# octanis_v0_2.net
KiCad netlist of a schematic drawn in EAGLE
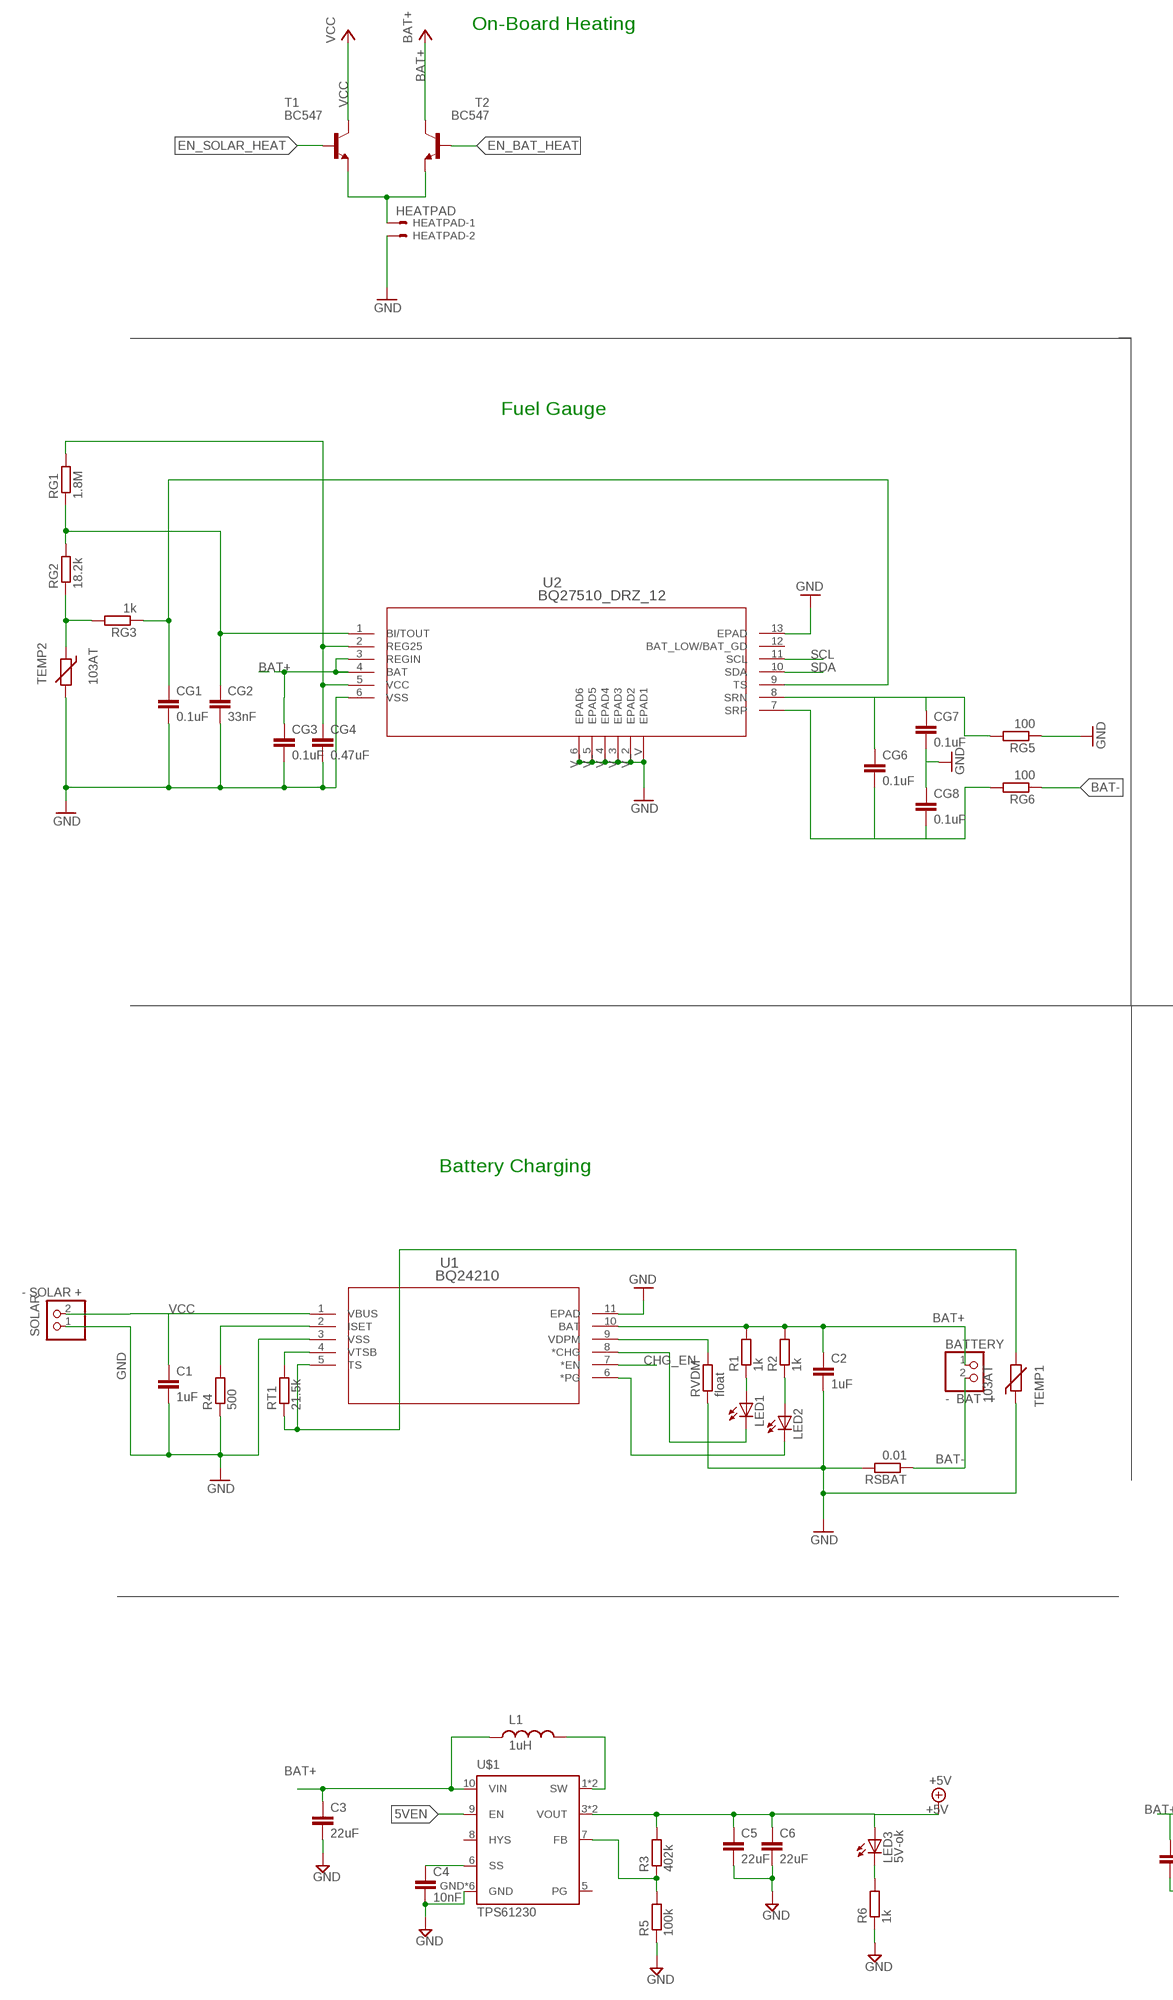
[diagram p0: schematic, sheet 1, part 1 of 3]
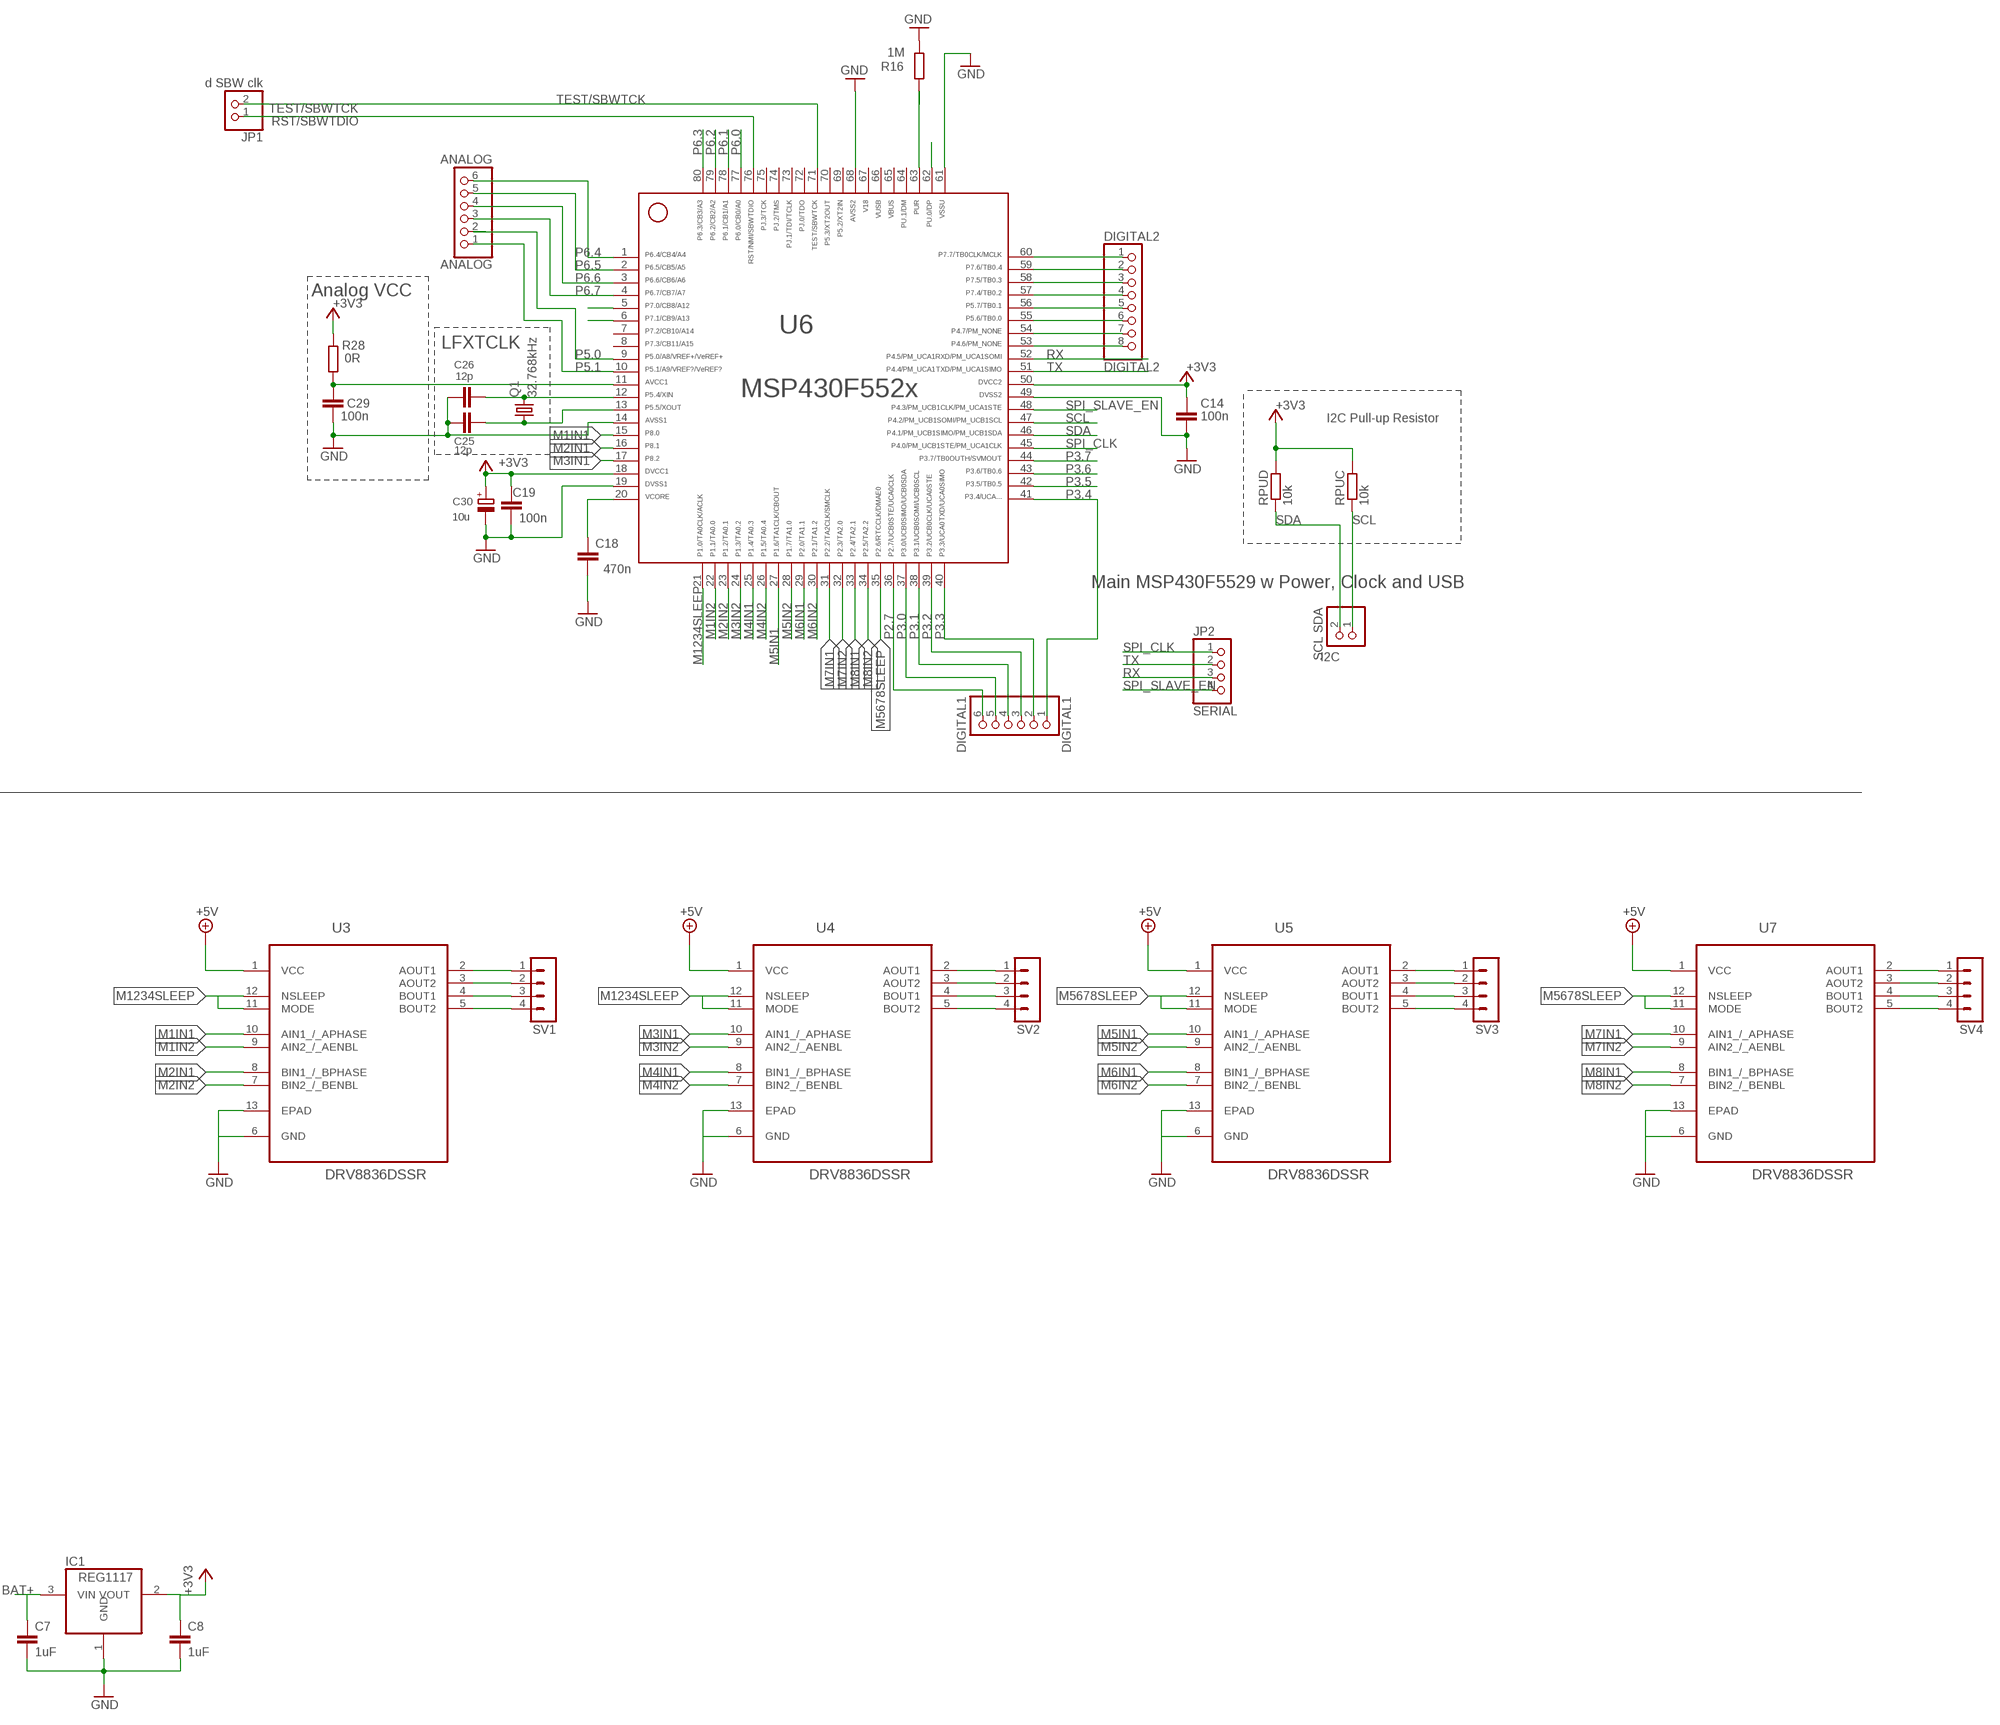
[diagram p1: schematic, sheet 1, part 2 of 3]
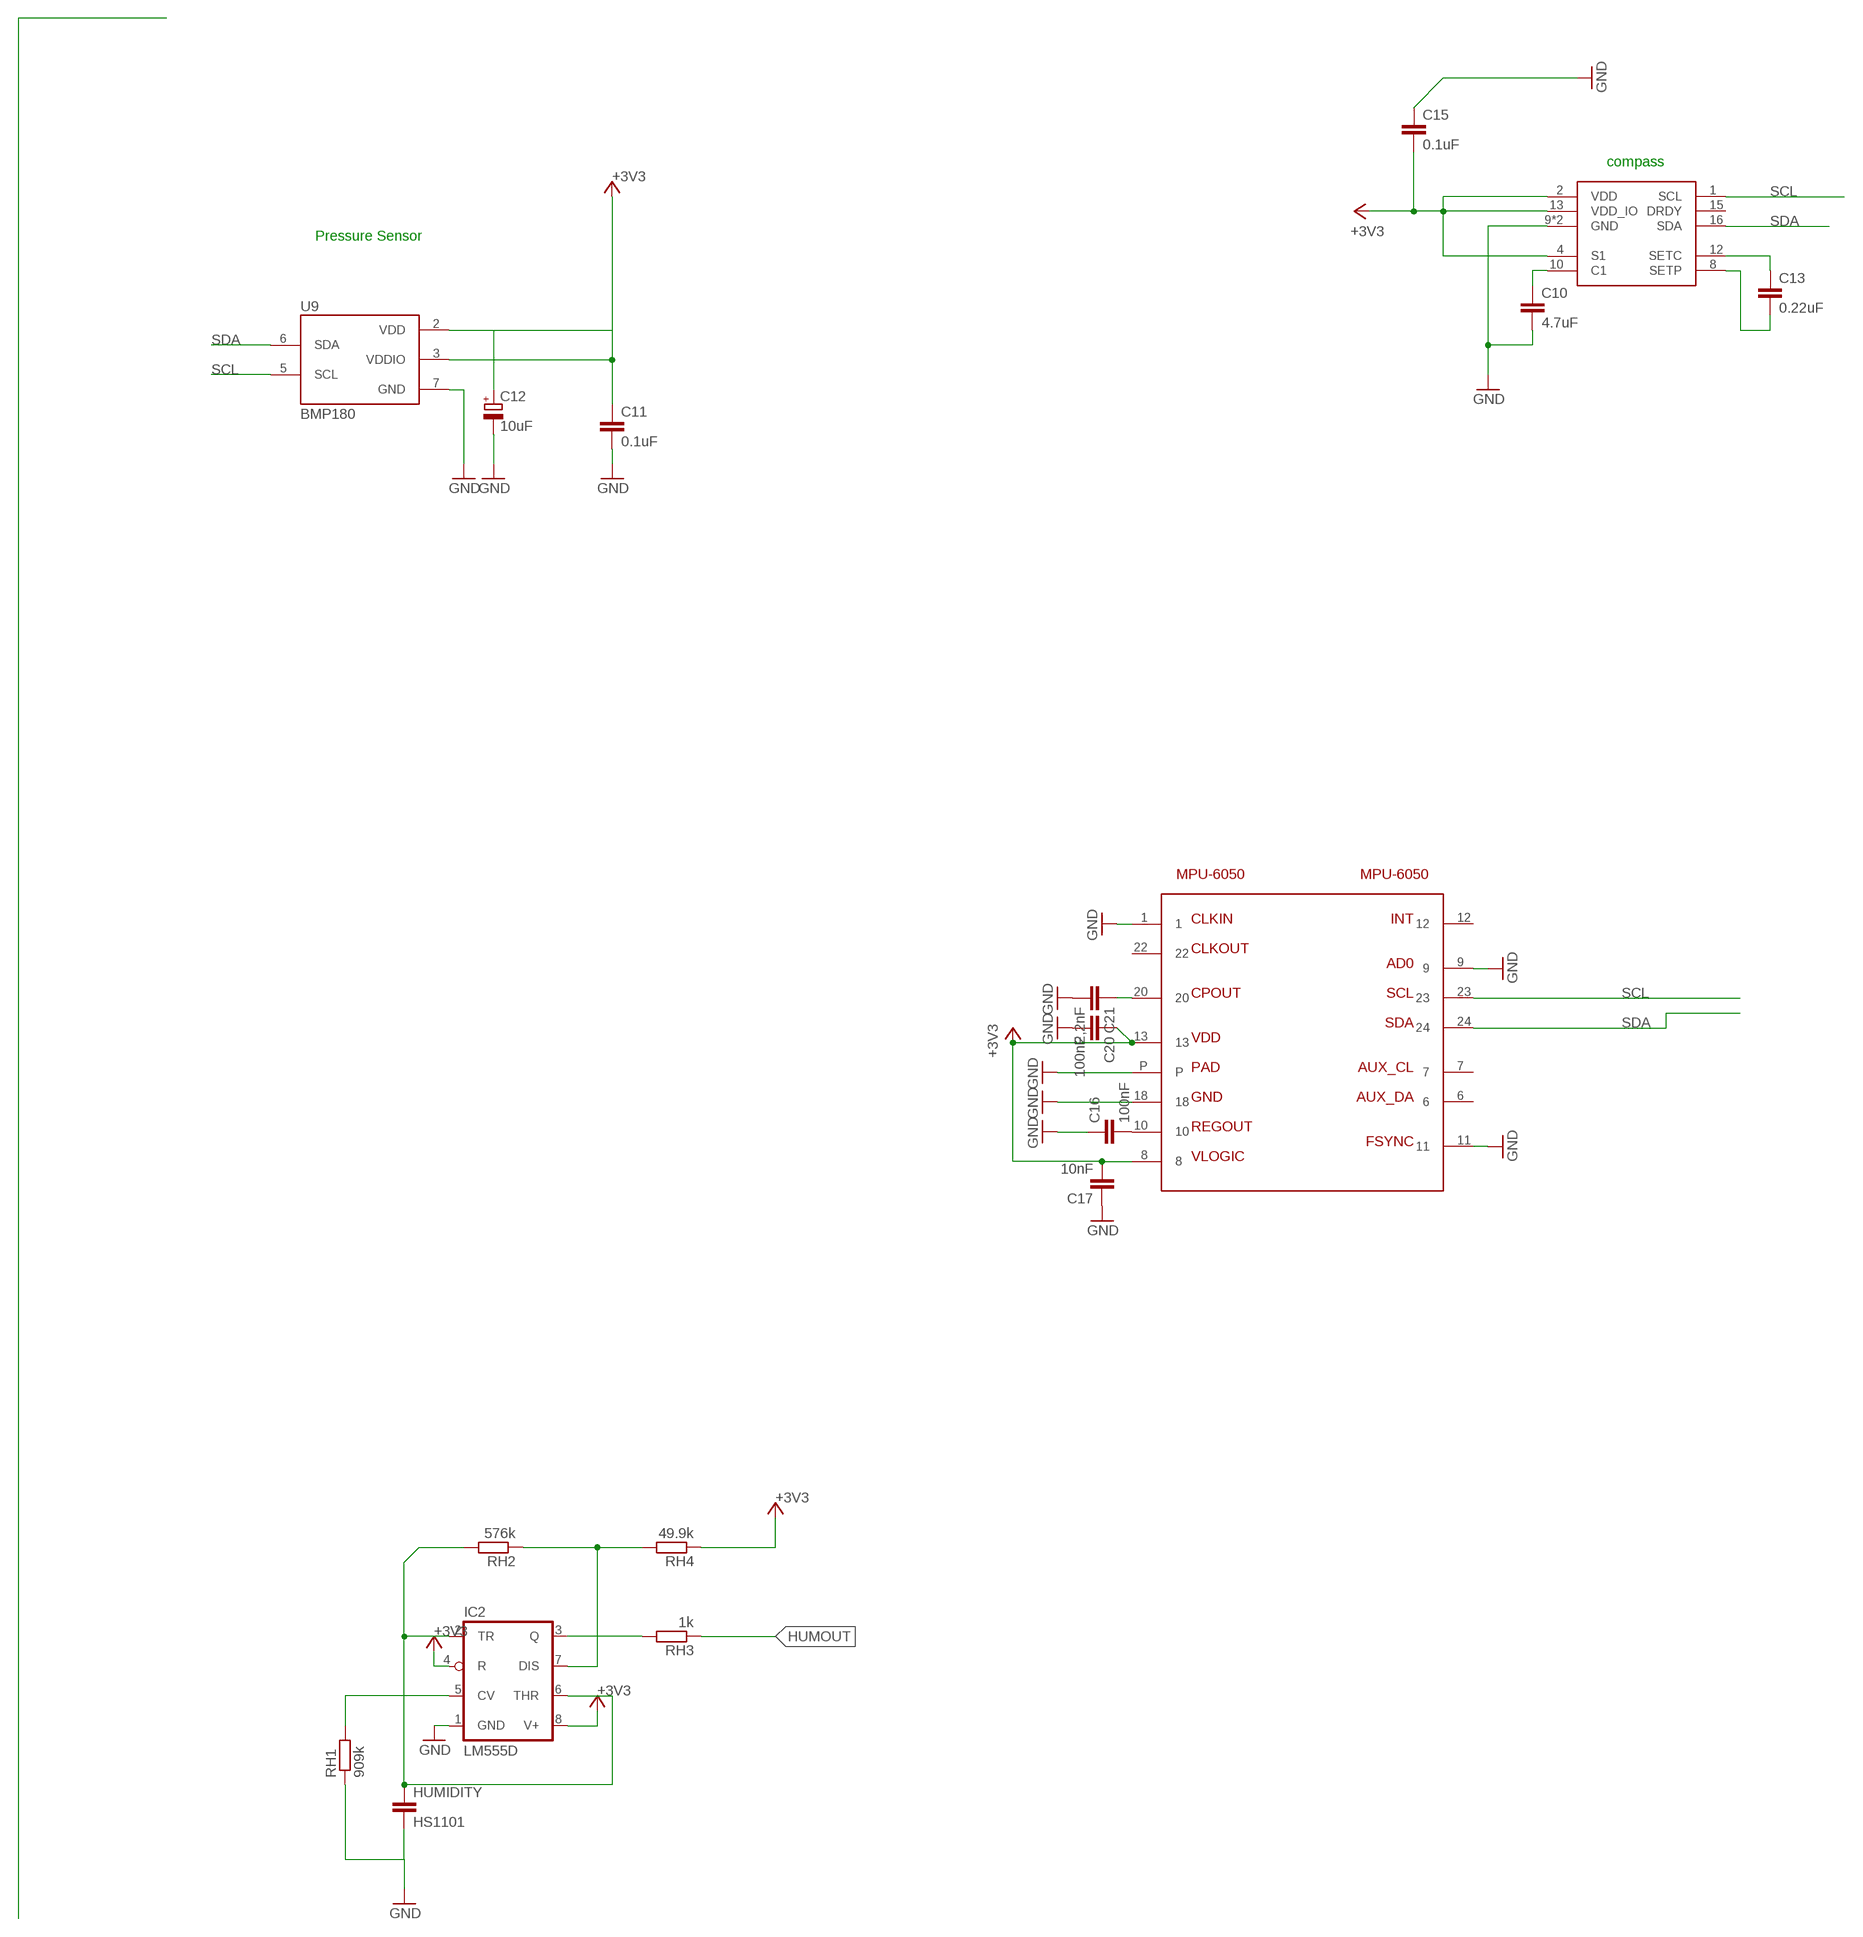
[diagram p2: schematic, sheet 1, part 3 of 3]

(export (version "E")
  (design (tool "Eeschema 10.0.6"))
  (components
    (comp (ref "ANALOG")
      (value "ANALOG")
      (footprint "eagle-import:1X06")
      (libsource (lib "eagle-import") (part "PINHD-1X6"))
    )
    (comp (ref "BATTERY")
      (value "- BAT +")
      (footprint "eagle-import:1X02")
      (libsource (lib "eagle-import") (part "PINHD-1X2"))
    )
    (comp (ref "C1")
      (value "1uF")
      (footprint "eagle-import:C1206")
      (libsource (lib "eagle-import") (part "C-EUC1206"))
    )
    (comp (ref "C2")
      (value "1uF")
      (footprint "eagle-import:C1206")
      (libsource (lib "eagle-import") (part "C-EUC1206"))
    )
    (comp (ref "C3")
      (value "22uF")
      (footprint "eagle-import:C0603")
      (libsource (lib "eagle-import") (part "C-EUC0603"))
    )
    (comp (ref "C4")
      (value "10nF")
      (footprint "eagle-import:C0603")
      (libsource (lib "eagle-import") (part "C-EUC0603"))
    )
    (comp (ref "C5")
      (value "22uF")
      (footprint "eagle-import:C0603")
      (libsource (lib "eagle-import") (part "C-EUC0603"))
    )
    (comp (ref "C6")
      (value "22uF")
      (footprint "eagle-import:C0603")
      (libsource (lib "eagle-import") (part "C-EUC0603"))
    )
    (comp (ref "C7")
      (value "1uF")
      (footprint "eagle-import:C0603")
      (libsource (lib "eagle-import") (part "C-EUC0603"))
    )
    (comp (ref "C8")
      (value "1uF")
      (footprint "eagle-import:C0603")
      (libsource (lib "eagle-import") (part "C-EUC0603"))
    )
    (comp (ref "C10")
      (value "4.7uF")
      (footprint "eagle-import:C0603")
      (libsource (lib "eagle-import") (part "C-EUC0603"))
    )
    (comp (ref "C11")
      (value "0.1uF")
      (footprint "eagle-import:C0603")
      (libsource (lib "eagle-import") (part "C-EUC0603"))
    )
    (comp (ref "C12")
      (value "10uF")
      (footprint "eagle-import:A_3216-18R")
      (libsource (lib "eagle-import") (part "resistor_CPOL-EUA/3216-18R"))
    )
    (comp (ref "C13")
      (value "0.22uF")
      (footprint "eagle-import:C0603")
      (libsource (lib "eagle-import") (part "C-EUC0603"))
    )
    (comp (ref "C14")
      (value "100n")
      (footprint "eagle-import:C0603")
      (libsource (lib "eagle-import") (part "C-EUC0603"))
    )
    (comp (ref "C15")
      (value "0.1uF")
      (footprint "eagle-import:C0603")
      (libsource (lib "eagle-import") (part "C-EUC0603"))
    )
    (comp (ref "C16")
      (value "100nF")
      (footprint "eagle-import:C0603")
      (libsource (lib "eagle-import") (part "C-EUC0603"))
    )
    (comp (ref "C17")
      (value "10nF")
      (footprint "eagle-import:C0603")
      (libsource (lib "eagle-import") (part "C-EUC0603"))
    )
    (comp (ref "C18")
      (value "470n")
      (footprint "eagle-import:C0603")
      (libsource (lib "eagle-import") (part "C-EUC0603"))
    )
    (comp (ref "C19")
      (value "100n")
      (footprint "eagle-import:C0603")
      (libsource (lib "eagle-import") (part "C-EUC0603"))
    )
    (comp (ref "C20")
      (value "100nF")
      (footprint "eagle-import:C0603")
      (libsource (lib "eagle-import") (part "C-EUC0603"))
    )
    (comp (ref "C21")
      (value "2,2nF")
      (footprint "eagle-import:C0603")
      (libsource (lib "eagle-import") (part "C-EUC0603"))
    )
    (comp (ref "C25")
      (value "12p")
      (footprint "eagle-import:C0603")
      (libsource (lib "eagle-import") (part "C-EUC0603"))
    )
    (comp (ref "C26")
      (value "12p")
      (footprint "eagle-import:C0603")
      (libsource (lib "eagle-import") (part "C-EUC0603"))
    )
    (comp (ref "C29")
      (value "100n")
      (footprint "eagle-import:C0603")
      (libsource (lib "eagle-import") (part "C-EUC0603"))
    )
    (comp (ref "C30")
      (value "10u")
      (footprint "eagle-import:A_3216-18R")
      (libsource (lib "eagle-import") (part "CPOL-EUA/3216-18R"))
    )
    (comp (ref "CG1")
      (value "0.1uF")
      (footprint "eagle-import:C0603")
      (libsource (lib "eagle-import") (part "C-EUC0603"))
    )
    (comp (ref "CG2")
      (value "33nF")
      (footprint "eagle-import:C0603")
      (libsource (lib "eagle-import") (part "C-EUC0603"))
    )
    (comp (ref "CG3")
      (value "0.1uF")
      (footprint "eagle-import:C0603")
      (libsource (lib "eagle-import") (part "C-EUC0603"))
    )
    (comp (ref "CG4")
      (value "0.47uF")
      (footprint "eagle-import:C0603")
      (libsource (lib "eagle-import") (part "C-EUC0603"))
    )
    (comp (ref "CG6")
      (value "0.1uF")
      (footprint "eagle-import:C0603")
      (libsource (lib "eagle-import") (part "C-EUC0603"))
    )
    (comp (ref "CG7")
      (value "0.1uF")
      (footprint "eagle-import:C0603")
      (libsource (lib "eagle-import") (part "C-EUC0603"))
    )
    (comp (ref "CG8")
      (value "0.1uF")
      (footprint "eagle-import:C0603")
      (libsource (lib "eagle-import") (part "C-EUC0603"))
    )
    (comp (ref "COMPASS")
      (value "HMC5883L")
      (footprint "eagle-import:LPCC16")
      (libsource (lib "eagle-import") (part "HMC5883L"))
    )
    (comp (ref "DIGITAL1")
      (value "DIGITAL1")
      (footprint "eagle-import:1X06")
      (libsource (lib "eagle-import") (part "PINHD-1X6"))
    )
    (comp (ref "DIGITAL2")
      (value "DIGITAL2")
      (footprint "eagle-import:1X08")
      (libsource (lib "eagle-import") (part "PINHD-1X8"))
    )
    (comp (ref "HEATPAD")
      (value "HEATPAD")
      (footprint "eagle-import:22-23-2021")
      (fields (field (name "MF") "MOLEX") (field (name "MPN") "22-23-2021"))
      (libsource (lib "eagle-import") (part "22-23-2021"))
    )
    (comp (ref "HUMIDITY")
      (value "HS1101")
      (footprint "eagle-import:C025-024X044")
      (libsource (lib "eagle-import") (part "C-EU025-024X044"))
    )
    (comp (ref "I2C")
      (value "SCL SDA")
      (footprint "eagle-import:1X02")
      (libsource (lib "eagle-import") (part "PINHD-1X2"))
    )
    (comp (ref "IC1")
      (value "REG1117")
      (footprint "eagle-import:SOT223")
      (libsource (lib "eagle-import") (part "REG1117"))
    )
    (comp (ref "IC2")
      (value "LM555D")
      (footprint "eagle-import:SO08")
      (libsource (lib "eagle-import") (part "555DLM"))
    )
    (comp (ref "JP1")
      (value "d SBW clk")
      (footprint "eagle-import:1X02")
      (libsource (lib "eagle-import") (part "PINHD-1X2"))
    )
    (comp (ref "JP2")
      (value "SERIAL")
      (footprint "eagle-import:1X04")
      (libsource (lib "eagle-import") (part "PINHD-1X4"))
    )
    (comp (ref "L1")
      (value "1uH")
      (footprint "eagle-import:XFL4020")
      (libsource (lib "eagle-import") (part "XFL4020"))
    )
    (comp (ref "LED1")
      (value "LEDCHIP-LED0603")
      (footprint "eagle-import:CHIP-LED0603")
      (libsource (lib "eagle-import") (part "led_LEDCHIP-LED0603"))
    )
    (comp (ref "LED2")
      (value "LEDCHIP-LED0603")
      (footprint "eagle-import:CHIP-LED0603")
      (libsource (lib "eagle-import") (part "led_LEDCHIP-LED0603"))
    )
    (comp (ref "LED3")
      (value "5V-ok")
      (footprint "eagle-import:CHIPLED_0603")
      (libsource (lib "eagle-import") (part "LEDCHIPLED_0603"))
    )
    (comp (ref "MPU-6050")
      (value "MPU-6050")
      (footprint "eagle-import:QFN24")
      (libsource (lib "eagle-import") (part "MPU-6050"))
    )
    (comp (ref "Q1")
      (value "32.768kHz")
      (footprint "eagle-import:FC-12M")
      (libsource (lib "eagle-import") (part "FC-12M"))
    )
    (comp (ref "R1")
      (value "1k")
      (footprint "eagle-import:R0603")
      (libsource (lib "eagle-import") (part "R-EU_R0603"))
    )
    (comp (ref "R2")
      (value "1k")
      (footprint "eagle-import:R0603")
      (libsource (lib "eagle-import") (part "R-EU_R0603"))
    )
    (comp (ref "R3")
      (value "402k")
      (footprint "eagle-import:R0603")
      (libsource (lib "eagle-import") (part "R-EU_R0603"))
    )
    (comp (ref "R4")
      (value "500")
      (footprint "eagle-import:R1206")
      (libsource (lib "eagle-import") (part "resistor_R-EU_R1206"))
    )
    (comp (ref "R5")
      (value "100k")
      (footprint "eagle-import:R0603")
      (libsource (lib "eagle-import") (part "R-EU_R0603"))
    )
    (comp (ref "R6")
      (value "1k")
      (footprint "eagle-import:R0603")
      (libsource (lib "eagle-import") (part "R-EU_R0603"))
    )
    (comp (ref "R16")
      (value "1M")
      (footprint "eagle-import:R0603")
      (libsource (lib "eagle-import") (part "R-EU_R0603"))
    )
    (comp (ref "R28")
      (value "0R")
      (footprint "eagle-import:R0603")
      (libsource (lib "eagle-import") (part "R-EU_R0603"))
    )
    (comp (ref "RG1")
      (value "1.8M")
      (footprint "eagle-import:R0603")
      (libsource (lib "eagle-import") (part "R-EU_R0603"))
    )
    (comp (ref "RG2")
      (value "18.2k")
      (footprint "eagle-import:R0603")
      (libsource (lib "eagle-import") (part "R-EU_R0603"))
    )
    (comp (ref "RG3")
      (value "1k")
      (footprint "eagle-import:R0603")
      (libsource (lib "eagle-import") (part "R-EU_R0603"))
    )
    (comp (ref "RG5")
      (value "100")
      (footprint "eagle-import:R0603")
      (libsource (lib "eagle-import") (part "R-EU_R0603"))
    )
    (comp (ref "RG6")
      (value "100")
      (footprint "eagle-import:R0603")
      (libsource (lib "eagle-import") (part "R-EU_R0603"))
    )
    (comp (ref "RH1")
      (value "909k")
      (footprint "eagle-import:R0603")
      (libsource (lib "eagle-import") (part "R-EU_R0603"))
    )
    (comp (ref "RH2")
      (value "576k")
      (footprint "eagle-import:R0603")
      (libsource (lib "eagle-import") (part "R-EU_R0603"))
    )
    (comp (ref "RH3")
      (value "1k")
      (footprint "eagle-import:R0603")
      (libsource (lib "eagle-import") (part "R-EU_R0603"))
    )
    (comp (ref "RH4")
      (value "49.9k")
      (footprint "eagle-import:R0603")
      (libsource (lib "eagle-import") (part "R-EU_R0603"))
    )
    (comp (ref "RPUC")
      (value "10k")
      (footprint "eagle-import:R0603")
      (libsource (lib "eagle-import") (part "R-EU_R0603"))
    )
    (comp (ref "RPUD")
      (value "10k")
      (footprint "eagle-import:R0603")
      (libsource (lib "eagle-import") (part "R-EU_R0603"))
    )
    (comp (ref "RSBAT")
      (value "0.01")
      (footprint "eagle-import:R1206")
      (libsource (lib "eagle-import") (part "resistor_R-EU_R1206"))
    )
    (comp (ref "RT1")
      (value "21.5k")
      (footprint "eagle-import:R1206")
      (libsource (lib "eagle-import") (part "resistor_R-EU_R1206"))
    )
    (comp (ref "RVDM")
      (value "float")
      (footprint "eagle-import:R1206")
      (libsource (lib "eagle-import") (part "resistor_R-EU_R1206"))
    )
    (comp (ref "SOLAR")
      (value "- SOLAR +")
      (footprint "eagle-import:1X02")
      (libsource (lib "eagle-import") (part "PINHD-1X2"))
    )
    (comp (ref "SV1")
      (value "MA04-1")
      (footprint "eagle-import:MA04-1")
      (libsource (lib "eagle-import") (part "MA04-1"))
    )
    (comp (ref "SV2")
      (value "MA04-1")
      (footprint "eagle-import:MA04-1")
      (libsource (lib "eagle-import") (part "MA04-1"))
    )
    (comp (ref "SV3")
      (value "MA04-1")
      (footprint "eagle-import:MA04-1")
      (libsource (lib "eagle-import") (part "MA04-1"))
    )
    (comp (ref "SV4")
      (value "MA04-1")
      (footprint "eagle-import:MA04-1")
      (libsource (lib "eagle-import") (part "MA04-1"))
    )
    (comp (ref "T1")
      (value "BC547")
      (footprint "eagle-import:TO92")
      (libsource (lib "eagle-import") (part "BC547"))
    )
    (comp (ref "T2")
      (value "BC547")
      (footprint "eagle-import:TO92")
      (libsource (lib "eagle-import") (part "BC547"))
    )
    (comp (ref "TEMP1")
      (value "103AT")
      (footprint "eagle-import:RS-2,5")
      (libsource (lib "eagle-import") (part "THERMISTOR-2,5"))
    )
    (comp (ref "TEMP2")
      (value "103AT")
      (footprint "eagle-import:RS-2,5")
      (libsource (lib "eagle-import") (part "THERMISTOR-2,5"))
    )
    (comp (ref "U$1")
      (value "TPS61230")
      (footprint "eagle-import:DRC-S-PVSON-N11")
      (libsource (lib "eagle-import") (part "TPS61230"))
    )
    (comp (ref "U1")
      (value "BQ24210")
      (footprint "eagle-import:DQC10_P84X2P4")
      (fields (field (name "MANUFACTURER") "Texas Instruments"))
      (libsource (lib "eagle-import") (part "BQ24210_DQC_10"))
    )
    (comp (ref "U2")
      (value "BQ27510_DRZ_12")
      (footprint "eagle-import:DRZ12_1P95X2P45")
      (fields
        (field (name "GENERIC_PART_NUMBER") "BQ27510")
        (field (name "MANUFACTURER") "Texas Instruments")
      )
      (libsource (lib "eagle-import") (part "BQ27510_DRZ_12"))
    )
    (comp (ref "U3")
      (value "DRV8836DSSR")
      (footprint "eagle-import:SON50P200X300X80-13N")
      (fields (field (name "MPN") "DRV8836DSSR "))
      (libsource (lib "eagle-import") (part "DRV8836DSSR"))
    )
    (comp (ref "U4")
      (value "DRV8836DSSR")
      (footprint "eagle-import:SON50P200X300X80-13N")
      (fields (field (name "MPN") "DRV8836DSSR "))
      (libsource (lib "eagle-import") (part "DRV8836DSSR"))
    )
    (comp (ref "U5")
      (value "DRV8836DSSR")
      (footprint "eagle-import:SON50P200X300X80-13N")
      (fields (field (name "MPN") "DRV8836DSSR "))
      (libsource (lib "eagle-import") (part "DRV8836DSSR"))
    )
    (comp (ref "U6")
      (value "MSP430F5529IPNR")
      (footprint "eagle-import:PN80")
      (libsource (lib "eagle-import") (part "F552X---PN80"))
    )
    (comp (ref "U7")
      (value "DRV8836DSSR")
      (footprint "eagle-import:SON50P200X300X80-13N")
      (fields (field (name "MPN") "DRV8836DSSR "))
      (libsource (lib "eagle-import") (part "DRV8836DSSR"))
    )
    (comp (ref "U9")
      (value "BMP180")
      (footprint "eagle-import:BMP180")
      (libsource (lib "eagle-import") (part "BMP180"))
    )
  )
  (nets
    (net (code "1") (name "+3V3") (class "Default")
      (node (ref "C11") (pin "1") (pinfunction "1_1") (pintype "passive"))
      (node (ref "C12") (pin "+") (pinfunction "+_+") (pintype "passive"))
      (node (ref "C14") (pin "1") (pinfunction "1_1") (pintype "passive"))
      (node (ref "C15") (pin "2") (pinfunction "2_2") (pintype "passive"))
      (node (ref "C17") (pin "2") (pinfunction "2_2") (pintype "passive"))
      (node (ref "C19") (pin "2") (pinfunction "2_2") (pintype "passive"))
      (node (ref "C20") (pin "1") (pinfunction "1_1") (pintype "passive"))
      (node (ref "C30") (pin "+") (pinfunction "+_+") (pintype "passive"))
      (node (ref "C8") (pin "1") (pinfunction "1_1") (pintype "passive"))
      (node (ref "COMPASS") (pin "13") (pinfunction "VDD_IO_13") (pintype "power_in"))
      (node (ref "COMPASS") (pin "2") (pinfunction "VDD_2") (pintype "power_in"))
      (node (ref "COMPASS") (pin "4") (pinfunction "S1_4") (pintype "power_in"))
      (node (ref "IC1") (pin "2") (pinfunction "VOUT_2") (pintype "output"))
      (node (ref "IC2") (pin "4") (pinfunction "R_4") (pintype "input"))
      (node (ref "IC2") (pin "8") (pinfunction "V+_8") (pintype "power_in"))
      (node (ref "MPU-6050") (pin "13") (pinfunction "13_13") (pintype "bidirectional"))
      (node (ref "MPU-6050") (pin "8") (pinfunction "8_8") (pintype "bidirectional"))
      (node (ref "R28") (pin "2") (pinfunction "2_2") (pintype "passive"))
      (node (ref "RH4") (pin "1") (pinfunction "1_1") (pintype "passive"))
      (node (ref "RPUC") (pin "2") (pinfunction "2_2") (pintype "passive"))
      (node (ref "RPUD") (pin "2") (pinfunction "2_2") (pintype "passive"))
      (node (ref "U6") (pin "18") (pinfunction "18_18") (pintype "power_in"))
      (node (ref "U6") (pin "50") (pinfunction "50_50") (pintype "power_in"))
      (node (ref "U9") (pin "2") (pinfunction "VDD_2") (pintype "power_in"))
      (node (ref "U9") (pin "3") (pinfunction "VDDIO_3") (pintype "power_in"))
    )
    (net (code "2") (name "+5V") (class "Default")
      (node (ref "C5") (pin "1") (pinfunction "1_1") (pintype "passive"))
      (node (ref "C6") (pin "1") (pinfunction "1_1") (pintype "passive"))
      (node (ref "LED3") (pin "A") (pinfunction "A_A") (pintype "passive"))
      (node (ref "R3") (pin "2") (pinfunction "2_2") (pintype "passive"))
      (node (ref "U$1") (pin "3") (pinfunction "VOUT_3") (pintype "passive"))
      (node (ref "U$1") (pin "4") (pinfunction "VOUT_4") (pintype "passive"))
      (node (ref "U3") (pin "1") (pinfunction "VCC_1") (pintype "power_in"))
      (node (ref "U4") (pin "1") (pinfunction "VCC_1") (pintype "power_in"))
      (node (ref "U5") (pin "1") (pinfunction "VCC_1") (pintype "power_in"))
      (node (ref "U7") (pin "1") (pinfunction "VCC_1") (pintype "power_in"))
    )
    (net (code "3") (name "/65") (class "Default")
      (node (ref "U6") (pin "65") (pinfunction "65_65") (pintype "power_in"))
    )
    (net (code "4") (name "/66") (class "Default")
      (node (ref "U6") (pin "66") (pinfunction "66_66") (pintype "power_in"))
    )
    (net (code "5") (name "/67") (class "Default")
      (node (ref "U6") (pin "67") (pinfunction "67_67") (pintype "power_in"))
    )
    (net (code "6") (name "/CHG_EN") (class "Default")
      (node (ref "U1") (pin "7") (pinfunction "*EN_7") (pintype "input"))
      (node (ref "U6") (pin "5") (pinfunction "5_5") (pintype "bidirectional"))
    )
    (net (code "7") (name "/P2.7") (class "Default")
      (node (ref "DIGITAL1") (pin "6") (pinfunction "6_6") (pintype "passive"))
      (node (ref "U6") (pin "36") (pinfunction "36_36") (pintype "bidirectional"))
    )
    (net (code "8") (name "/P3.0") (class "Default")
      (node (ref "DIGITAL1") (pin "5") (pinfunction "5_5") (pintype "passive"))
      (node (ref "U6") (pin "37") (pinfunction "37_37") (pintype "bidirectional"))
    )
    (net (code "9") (name "/P3.1") (class "Default")
      (node (ref "DIGITAL1") (pin "4") (pinfunction "4_4") (pintype "passive"))
      (node (ref "U6") (pin "38") (pinfunction "38_38") (pintype "bidirectional"))
    )
    (net (code "10") (name "/P3.2") (class "Default")
      (node (ref "DIGITAL1") (pin "3") (pinfunction "3_3") (pintype "passive"))
      (node (ref "U6") (pin "39") (pinfunction "39_39") (pintype "bidirectional"))
    )
    (net (code "11") (name "/P3.3") (class "Default")
      (node (ref "DIGITAL1") (pin "2") (pinfunction "2_2") (pintype "passive"))
      (node (ref "U6") (pin "40") (pinfunction "40_40") (pintype "bidirectional"))
    )
    (net (code "12") (name "/P3.4") (class "Default")
      (node (ref "DIGITAL1") (pin "1") (pinfunction "1_1") (pintype "passive"))
      (node (ref "U6") (pin "41") (pinfunction "41_41") (pintype "bidirectional"))
    )
    (net (code "13") (name "/P3.5") (class "Default")
      (node (ref "U6") (pin "42") (pinfunction "42_42") (pintype "bidirectional"))
    )
    (net (code "14") (name "/P3.6") (class "Default")
      (node (ref "U6") (pin "43") (pinfunction "43_43") (pintype "bidirectional"))
    )
    (net (code "15") (name "/P3.7") (class "Default")
      (node (ref "U6") (pin "44") (pinfunction "44_44") (pintype "bidirectional"))
    )
    (net (code "16") (name "/P5.0") (class "Default")
      (node (ref "ANALOG") (pin "2") (pinfunction "2_2") (pintype "passive"))
      (node (ref "U6") (pin "9") (pinfunction "9_9") (pintype "bidirectional"))
    )
    (net (code "17") (name "/P5.1") (class "Default")
      (node (ref "ANALOG") (pin "1") (pinfunction "1_1") (pintype "passive"))
      (node (ref "U6") (pin "10") (pinfunction "10_10") (pintype "bidirectional"))
    )
    (net (code "18") (name "/P6.0") (class "Default")
      (node (ref "U6") (pin "77") (pinfunction "77_77") (pintype "bidirectional"))
    )
    (net (code "19") (name "/P6.1") (class "Default")
      (node (ref "U6") (pin "78") (pinfunction "78_78") (pintype "bidirectional"))
    )
    (net (code "20") (name "/P6.2") (class "Default")
      (node (ref "U6") (pin "79") (pinfunction "79_79") (pintype "bidirectional"))
    )
    (net (code "21") (name "/P6.3") (class "Default")
      (node (ref "U6") (pin "80") (pinfunction "80_80") (pintype "bidirectional"))
    )
    (net (code "22") (name "/P6.4") (class "Default")
      (node (ref "ANALOG") (pin "6") (pinfunction "6_6") (pintype "passive"))
      (node (ref "U6") (pin "1") (pinfunction "1_1") (pintype "bidirectional"))
    )
    (net (code "23") (name "/P6.5") (class "Default")
      (node (ref "ANALOG") (pin "5") (pinfunction "5_5") (pintype "passive"))
      (node (ref "U6") (pin "2") (pinfunction "2_2") (pintype "bidirectional"))
    )
    (net (code "24") (name "/P6.6") (class "Default")
      (node (ref "ANALOG") (pin "4") (pinfunction "4_4") (pintype "passive"))
      (node (ref "U6") (pin "3") (pinfunction "3_3") (pintype "bidirectional"))
    )
    (net (code "25") (name "/P6.7") (class "Default")
      (node (ref "ANALOG") (pin "3") (pinfunction "3_3") (pintype "passive"))
      (node (ref "U6") (pin "4") (pinfunction "4_4") (pintype "bidirectional"))
    )
    (net (code "26") (name "/PG") (class "Default")
      (node (ref "U$1") (pin "5") (pinfunction "PG_5") (pintype "power_in"))
    )
    (net (code "27") (name "/RST{slash}SBWTDIO") (class "Default")
      (node (ref "JP1") (pin "1") (pinfunction "1_1") (pintype "passive"))
      (node (ref "U6") (pin "76") (pinfunction "76_76") (pintype "bidirectional"))
    )
    (net (code "28") (name "/RX") (class "Default")
      (node (ref "JP2") (pin "3") (pinfunction "3_3") (pintype "passive"))
      (node (ref "U6") (pin "52") (pinfunction "52_52") (pintype "bidirectional"))
    )
    (net (code "29") (name "/SCL") (class "Default")
      (node (ref "COMPASS") (pin "1") (pinfunction "SCL_1") (pintype "input"))
      (node (ref "I2C") (pin "1") (pinfunction "1_1") (pintype "passive"))
      (node (ref "MPU-6050") (pin "23") (pinfunction "23_23") (pintype "bidirectional"))
      (node (ref "RPUC") (pin "1") (pinfunction "1_1") (pintype "passive"))
      (node (ref "U2") (pin "11") (pinfunction "SCL_11") (pintype "input"))
      (node (ref "U6") (pin "47") (pinfunction "47_47") (pintype "bidirectional"))
      (node (ref "U9") (pin "5") (pinfunction "SCL_5") (pintype "input"))
    )
    (net (code "30") (name "/SDA") (class "Default")
      (node (ref "COMPASS") (pin "16") (pinfunction "SDA_16") (pintype "input"))
      (node (ref "I2C") (pin "2") (pinfunction "2_2") (pintype "passive"))
      (node (ref "MPU-6050") (pin "24") (pinfunction "24_24") (pintype "bidirectional"))
      (node (ref "RPUD") (pin "1") (pinfunction "1_1") (pintype "passive"))
      (node (ref "U2") (pin "10") (pinfunction "SDA_10") (pintype "bidirectional"))
      (node (ref "U6") (pin "46") (pinfunction "46_46") (pintype "bidirectional"))
      (node (ref "U9") (pin "6") (pinfunction "SDA_6") (pintype "bidirectional"))
    )
    (net (code "31") (name "/SPI_CLK") (class "Default")
      (node (ref "JP2") (pin "1") (pinfunction "1_1") (pintype "passive"))
      (node (ref "U6") (pin "45") (pinfunction "45_45") (pintype "bidirectional"))
    )
    (net (code "32") (name "/SPI_SLAVE_EN") (class "Default")
      (node (ref "JP2") (pin "4") (pinfunction "4_4") (pintype "passive"))
      (node (ref "U6") (pin "48") (pinfunction "48_48") (pintype "bidirectional"))
    )
    (net (code "33") (name "/TEST{slash}SBWTCK") (class "Default")
      (node (ref "JP1") (pin "2") (pinfunction "2_2") (pintype "passive"))
      (node (ref "U6") (pin "71") (pinfunction "71_71") (pintype "input"))
    )
    (net (code "34") (name "/TX") (class "Default")
      (node (ref "JP2") (pin "2") (pinfunction "2_2") (pintype "passive"))
      (node (ref "U6") (pin "51") (pinfunction "51_51") (pintype "bidirectional"))
    )
    (net (code "35") (name "5VEN") (class "Default")
      (node (ref "U$1") (pin "9") (pinfunction "EN_9") (pintype "input"))
      (node (ref "U6") (pin "6") (pinfunction "6_6") (pintype "bidirectional"))
    )
    (net (code "36") (name "BAT+") (class "Default")
      (node (ref "BATTERY") (pin "1") (pinfunction "1_1") (pintype "passive"))
      (node (ref "C2") (pin "1") (pinfunction "1_1") (pintype "passive"))
      (node (ref "C3") (pin "1") (pinfunction "1_1") (pintype "passive"))
      (node (ref "C7") (pin "1") (pinfunction "1_1") (pintype "passive"))
      (node (ref "CG3") (pin "1") (pinfunction "1_1") (pintype "passive"))
      (node (ref "IC1") (pin "3") (pinfunction "VIN_3") (pintype "input"))
      (node (ref "L1") (pin "P$1") (pinfunction "1_P$1") (pintype "passive"))
      (node (ref "R1") (pin "2") (pinfunction "2_2") (pintype "passive"))
      (node (ref "R2") (pin "2") (pinfunction "2_2") (pintype "passive"))
      (node (ref "T2") (pin "3") (pinfunction "C_3") (pintype "passive"))
      (node (ref "U$1") (pin "10") (pinfunction "VIN_10") (pintype "input"))
      (node (ref "U1") (pin "10") (pinfunction "BAT_10") (pintype "bidirectional"))
      (node (ref "U2") (pin "3") (pinfunction "REGIN_3") (pintype "power_in"))
      (node (ref "U2") (pin "4") (pinfunction "BAT_4") (pintype "input"))
    )
    (net (code "37") (name "BAT-") (class "Default")
      (node (ref "BATTERY") (pin "2") (pinfunction "2_2") (pintype "passive"))
      (node (ref "RG6") (pin "1") (pinfunction "1_1") (pintype "passive"))
      (node (ref "RSBAT") (pin "1") (pinfunction "1_1") (pintype "passive"))
    )
    (net (code "38") (name "EN_BAT_HEAT") (class "Default")
      (node (ref "T2") (pin "2") (pinfunction "B_2") (pintype "passive"))
    )
    (net (code "39") (name "EN_SOLAR_HEAT") (class "Default")
      (node (ref "T1") (pin "2") (pinfunction "B_2") (pintype "passive"))
    )
    (net (code "40") (name "GND") (class "Default")
      (node (ref "C1") (pin "2") (pinfunction "2_2") (pintype "passive"))
      (node (ref "C10") (pin "2") (pinfunction "2_2") (pintype "passive"))
      (node (ref "C11") (pin "2") (pinfunction "2_2") (pintype "passive"))
      (node (ref "C12") (pin "-") (pinfunction "-_-") (pintype "passive"))
      (node (ref "C14") (pin "2") (pinfunction "2_2") (pintype "passive"))
      (node (ref "C15") (pin "1") (pinfunction "1_1") (pintype "passive"))
      (node (ref "C16") (pin "1") (pinfunction "1_1") (pintype "passive"))
      (node (ref "C17") (pin "1") (pinfunction "1_1") (pintype "passive"))
      (node (ref "C18") (pin "1") (pinfunction "1_1") (pintype "passive"))
      (node (ref "C19") (pin "1") (pinfunction "1_1") (pintype "passive"))
      (node (ref "C2") (pin "2") (pinfunction "2_2") (pintype "passive"))
      (node (ref "C20") (pin "2") (pinfunction "2_2") (pintype "passive"))
      (node (ref "C21") (pin "2") (pinfunction "2_2") (pintype "passive"))
      (node (ref "C25") (pin "1") (pinfunction "1_1") (pintype "passive"))
      (node (ref "C26") (pin "1") (pinfunction "1_1") (pintype "passive"))
      (node (ref "C29") (pin "2") (pinfunction "2_2") (pintype "passive"))
      (node (ref "C3") (pin "2") (pinfunction "2_2") (pintype "passive"))
      (node (ref "C30") (pin "-") (pinfunction "-_-") (pintype "passive"))
      (node (ref "C4") (pin "2") (pinfunction "2_2") (pintype "passive"))
      (node (ref "C5") (pin "2") (pinfunction "2_2") (pintype "passive"))
      (node (ref "C6") (pin "2") (pinfunction "2_2") (pintype "passive"))
      (node (ref "C7") (pin "2") (pinfunction "2_2") (pintype "passive"))
      (node (ref "C8") (pin "2") (pinfunction "2_2") (pintype "passive"))
      (node (ref "CG1") (pin "2") (pinfunction "2_2") (pintype "passive"))
      (node (ref "CG2") (pin "2") (pinfunction "2_2") (pintype "passive"))
      (node (ref "CG3") (pin "2") (pinfunction "2_2") (pintype "passive"))
      (node (ref "CG4") (pin "2") (pinfunction "2_2") (pintype "passive"))
      (node (ref "CG7") (pin "2") (pinfunction "2_2") (pintype "passive"))
      (node (ref "CG8") (pin "1") (pinfunction "1_1") (pintype "passive"))
      (node (ref "COMPASS") (pin "11") (pinfunction "GND_11") (pintype "bidirectional"))
      (node (ref "COMPASS") (pin "9") (pinfunction "GND_9") (pintype "bidirectional"))
      (node (ref "HEATPAD") (pin "2") (pinfunction "S_2") (pintype "passive"))
      (node (ref "HUMIDITY") (pin "2") (pinfunction "2_2") (pintype "passive"))
      (node (ref "IC1") (pin "1") (pinfunction "GND_1") (pintype "power_in"))
      (node (ref "IC2") (pin "1") (pinfunction "GND_1") (pintype "power_in"))
      (node (ref "MPU-6050") (pin "1") (pinfunction "1_1") (pintype "bidirectional"))
      (node (ref "MPU-6050") (pin "11") (pinfunction "11_11") (pintype "bidirectional"))
      (node (ref "MPU-6050") (pin "18") (pinfunction "18_18") (pintype "bidirectional"))
      (node (ref "MPU-6050") (pin "9") (pinfunction "9_9") (pintype "bidirectional"))
      (node (ref "MPU-6050") (pin "P") (pinfunction "P_P") (pintype "bidirectional"))
      (node (ref "R16") (pin "1") (pinfunction "1_1") (pintype "passive"))
      (node (ref "R4") (pin "1") (pinfunction "1_1") (pintype "passive"))
      (node (ref "R5") (pin "1") (pinfunction "1_1") (pintype "passive"))
      (node (ref "R6") (pin "1") (pinfunction "1_1") (pintype "passive"))
      (node (ref "RG5") (pin "1") (pinfunction "1_1") (pintype "passive"))
      (node (ref "RH1") (pin "1") (pinfunction "1_1") (pintype "passive"))
      (node (ref "RSBAT") (pin "2") (pinfunction "2_2") (pintype "passive"))
      (node (ref "RVDM") (pin "1") (pinfunction "1_1") (pintype "passive"))
      (node (ref "SOLAR") (pin "1") (pinfunction "1_1") (pintype "passive"))
      (node (ref "TEMP1") (pin "1") (pinfunction "1_1") (pintype "passive"))
      (node (ref "TEMP2") (pin "2") (pinfunction "2_2") (pintype "passive"))
      (node (ref "U$1") (pin "GND") (pinfunction "GND_GND") (pintype "power_in"))
      (node (ref "U$1") (pin "GND@1") (pinfunction "GND_GND@1") (pintype "power_in"))
      (node (ref "U$1") (pin "GND@2") (pinfunction "GND_GND@2") (pintype "power_in"))
      (node (ref "U$1") (pin "GND@3") (pinfunction "GND_GND@3") (pintype "power_in"))
      (node (ref "U$1") (pin "GND@4") (pinfunction "GND_GND@4") (pintype "power_in"))
      (node (ref "U$1") (pin "GND@5") (pinfunction "GND_GND@5") (pintype "power_in"))
      (node (ref "U1") (pin "11") (pinfunction "EPAD_11") (pintype "power_in"))
      (node (ref "U1") (pin "3") (pinfunction "VSS_3") (pintype "power_in"))
      (node (ref "U2") (pin "13") (pinfunction "EPAD_13") (pintype "power_in"))
      (node (ref "U2") (pin "6") (pinfunction "VSS_6") (pintype "power_in"))
      (node (ref "U2") (pin "V") (pinfunction "EPAD1_V") (pintype "power_in"))
      (node (ref "U2") (pin "V_2") (pinfunction "EPAD2_V_2") (pintype "power_in"))
      (node (ref "U2") (pin "V_3") (pinfunction "EPAD3_V_3") (pintype "power_in"))
      (node (ref "U2") (pin "V_4") (pinfunction "EPAD4_V_4") (pintype "power_in"))
      (node (ref "U2") (pin "V_5") (pinfunction "EPAD5_V_5") (pintype "power_in"))
      (node (ref "U2") (pin "V_6") (pinfunction "EPAD6_V_6") (pintype "power_in"))
      (node (ref "U3") (pin "13") (pinfunction "EPAD_13") (pintype "passive"))
      (node (ref "U3") (pin "6") (pinfunction "GND_6") (pintype "passive"))
      (node (ref "U4") (pin "13") (pinfunction "EPAD_13") (pintype "passive"))
      (node (ref "U4") (pin "6") (pinfunction "GND_6") (pintype "passive"))
      (node (ref "U5") (pin "13") (pinfunction "EPAD_13") (pintype "passive"))
      (node (ref "U5") (pin "6") (pinfunction "GND_6") (pintype "passive"))
      (node (ref "U6") (pin "14") (pinfunction "14_14") (pintype "power_in"))
      (node (ref "U6") (pin "19") (pinfunction "19_19") (pintype "power_in"))
      (node (ref "U6") (pin "49") (pinfunction "49_49") (pintype "power_in"))
      (node (ref "U6") (pin "61") (pinfunction "61_61") (pintype "power_in"))
      (node (ref "U6") (pin "68") (pinfunction "68_68") (pintype "power_in"))
      (node (ref "U7") (pin "13") (pinfunction "EPAD_13") (pintype "passive"))
      (node (ref "U7") (pin "6") (pinfunction "GND_6") (pintype "passive"))
      (node (ref "U9") (pin "7") (pinfunction "GND_7") (pintype "power_in"))
    )
    (net (code "41") (name "HUMOUT") (class "Default")
      (node (ref "RH3") (pin "1") (pinfunction "1_1") (pintype "passive"))
    )
    (net (code "42") (name "M1IN1") (class "Default")
      (node (ref "U3") (pin "10") (pinfunction "AIN1_/_APHASE_10") (pintype "input"))
      (node (ref "U6") (pin "15") (pinfunction "15_15") (pintype "bidirectional"))
    )
    (net (code "43") (name "M1IN2") (class "Default")
      (node (ref "U3") (pin "9") (pinfunction "AIN2_/_AENBL_9") (pintype "input"))
      (node (ref "U6") (pin "22") (pinfunction "22_22") (pintype "bidirectional"))
    )
    (net (code "44") (name "M2IN1") (class "Default")
      (node (ref "U3") (pin "8") (pinfunction "BIN1_/_BPHASE_8") (pintype "input"))
      (node (ref "U6") (pin "16") (pinfunction "16_16") (pintype "bidirectional"))
    )
    (net (code "45") (name "M2IN2") (class "Default")
      (node (ref "U3") (pin "7") (pinfunction "BIN2_/_BENBL_7") (pintype "input"))
      (node (ref "U6") (pin "23") (pinfunction "23_23") (pintype "bidirectional"))
    )
    (net (code "46") (name "M3IN1") (class "Default")
      (node (ref "U4") (pin "10") (pinfunction "AIN1_/_APHASE_10") (pintype "input"))
      (node (ref "U6") (pin "17") (pinfunction "17_17") (pintype "bidirectional"))
    )
    (net (code "47") (name "M3IN2") (class "Default")
      (node (ref "U4") (pin "9") (pinfunction "AIN2_/_AENBL_9") (pintype "input"))
      (node (ref "U6") (pin "24") (pinfunction "24_24") (pintype "bidirectional"))
    )
    (net (code "48") (name "M4IN1") (class "Default")
      (node (ref "U4") (pin "8") (pinfunction "BIN1_/_BPHASE_8") (pintype "input"))
      (node (ref "U6") (pin "25") (pinfunction "25_25") (pintype "bidirectional"))
    )
    (net (code "49") (name "M4IN2") (class "Default")
      (node (ref "U4") (pin "7") (pinfunction "BIN2_/_BENBL_7") (pintype "input"))
      (node (ref "U6") (pin "26") (pinfunction "26_26") (pintype "bidirectional"))
    )
    (net (code "50") (name "M5IN1") (class "Default")
      (node (ref "U5") (pin "10") (pinfunction "AIN1_/_APHASE_10") (pintype "input"))
      (node (ref "U6") (pin "27") (pinfunction "27_27") (pintype "bidirectional"))
    )
    (net (code "51") (name "M5IN2") (class "Default")
      (node (ref "U5") (pin "9") (pinfunction "AIN2_/_AENBL_9") (pintype "input"))
      (node (ref "U6") (pin "28") (pinfunction "28_28") (pintype "bidirectional"))
    )
    (net (code "52") (name "M6IN1") (class "Default")
      (node (ref "U5") (pin "8") (pinfunction "BIN1_/_BPHASE_8") (pintype "input"))
      (node (ref "U6") (pin "29") (pinfunction "29_29") (pintype "bidirectional"))
    )
    (net (code "53") (name "M6IN2") (class "Default")
      (node (ref "U5") (pin "7") (pinfunction "BIN2_/_BENBL_7") (pintype "input"))
      (node (ref "U6") (pin "30") (pinfunction "30_30") (pintype "bidirectional"))
    )
    (net (code "54") (name "M7IN1") (class "Default")
      (node (ref "U6") (pin "31") (pinfunction "31_31") (pintype "bidirectional"))
      (node (ref "U7") (pin "10") (pinfunction "AIN1_/_APHASE_10") (pintype "input"))
    )
    (net (code "55") (name "M7IN2") (class "Default")
      (node (ref "U6") (pin "32") (pinfunction "32_32") (pintype "bidirectional"))
      (node (ref "U7") (pin "9") (pinfunction "AIN2_/_AENBL_9") (pintype "input"))
    )
    (net (code "56") (name "M8IN1") (class "Default")
      (node (ref "U6") (pin "33") (pinfunction "33_33") (pintype "bidirectional"))
      (node (ref "U7") (pin "8") (pinfunction "BIN1_/_BPHASE_8") (pintype "input"))
    )
    (net (code "57") (name "M8IN2") (class "Default")
      (node (ref "U6") (pin "34") (pinfunction "34_34") (pintype "bidirectional"))
      (node (ref "U7") (pin "7") (pinfunction "BIN2_/_BENBL_7") (pintype "input"))
    )
    (net (code "58") (name "M1234SLEEP") (class "Default")
      (node (ref "U3") (pin "11") (pinfunction "MODE_11") (pintype "input"))
      (node (ref "U3") (pin "12") (pinfunction "NSLEEP_12") (pintype "input"))
      (node (ref "U4") (pin "11") (pinfunction "MODE_11") (pintype "input"))
      (node (ref "U4") (pin "12") (pinfunction "NSLEEP_12") (pintype "input"))
      (node (ref "U6") (pin "21") (pinfunction "21_21") (pintype "bidirectional"))
    )
    (net (code "59") (name "M5678SLEEP") (class "Default")
      (node (ref "U5") (pin "11") (pinfunction "MODE_11") (pintype "input"))
      (node (ref "U5") (pin "12") (pinfunction "NSLEEP_12") (pintype "input"))
      (node (ref "U6") (pin "35") (pinfunction "35_35") (pintype "bidirectional"))
      (node (ref "U7") (pin "11") (pinfunction "MODE_11") (pintype "input"))
      (node (ref "U7") (pin "12") (pinfunction "NSLEEP_12") (pintype "input"))
    )
    (net (code "60") (name "Net-(C16-Pad2)") (class "Default")
      (node (ref "C16") (pin "2") (pinfunction "2_2") (pintype "passive"))
      (node (ref "MPU-6050") (pin "10") (pinfunction "10_10") (pintype "bidirectional"))
    )
    (net (code "61") (name "Net-(C18-Pad2)") (class "Default")
      (node (ref "C18") (pin "2") (pinfunction "2_2") (pintype "passive"))
      (node (ref "U6") (pin "20") (pinfunction "20_20") (pintype "power_in"))
    )
    (net (code "62") (name "Net-(C21-Pad1)") (class "Default")
      (node (ref "C21") (pin "1") (pinfunction "1_1") (pintype "passive"))
      (node (ref "MPU-6050") (pin "20") (pinfunction "20_20") (pintype "bidirectional"))
    )
    (net (code "63") (name "Net-(C25-Pad2)") (class "Default")
      (node (ref "C25") (pin "2") (pinfunction "2_2") (pintype "passive"))
      (node (ref "Q1") (pin "1") (pinfunction "1_1") (pintype "passive"))
      (node (ref "U6") (pin "13") (pinfunction "13_13") (pintype "bidirectional"))
    )
    (net (code "64") (name "Net-(C26-Pad2)") (class "Default")
      (node (ref "C26") (pin "2") (pinfunction "2_2") (pintype "passive"))
      (node (ref "Q1") (pin "2") (pinfunction "2_2") (pintype "passive"))
      (node (ref "U6") (pin "12") (pinfunction "12_12") (pintype "bidirectional"))
    )
    (net (code "65") (name "Net-(C29-Pad1)") (class "Default")
      (node (ref "C29") (pin "1") (pinfunction "1_1") (pintype "passive"))
      (node (ref "R28") (pin "1") (pinfunction "1_1") (pintype "passive"))
      (node (ref "U6") (pin "11") (pinfunction "11_11") (pintype "power_in"))
    )
    (net (code "66") (name "Net-(COMPASS-C1)") (class "Default")
      (node (ref "C10") (pin "1") (pinfunction "1_1") (pintype "passive"))
      (node (ref "COMPASS") (pin "10") (pinfunction "C1_10") (pintype "passive"))
    )
    (net (code "67") (name "Net-(COMPASS-SETC)") (class "Default")
      (node (ref "C13") (pin "1") (pinfunction "1_1") (pintype "passive"))
      (node (ref "COMPASS") (pin "12") (pinfunction "SETC_12") (pintype "passive"))
    )
    (net (code "68") (name "Net-(COMPASS-SETP)") (class "Default")
      (node (ref "C13") (pin "2") (pinfunction "2_2") (pintype "passive"))
      (node (ref "COMPASS") (pin "8") (pinfunction "SETP_8") (pintype "passive"))
    )
    (net (code "69") (name "Net-(DIGITAL2-Pad1)") (class "Default")
      (node (ref "DIGITAL2") (pin "1") (pinfunction "1_1") (pintype "passive"))
      (node (ref "U6") (pin "60") (pinfunction "60_60") (pintype "bidirectional"))
    )
    (net (code "70") (name "Net-(DIGITAL2-Pad2)") (class "Default")
      (node (ref "DIGITAL2") (pin "2") (pinfunction "2_2") (pintype "passive"))
      (node (ref "U6") (pin "59") (pinfunction "59_59") (pintype "bidirectional"))
    )
    (net (code "71") (name "Net-(DIGITAL2-Pad3)") (class "Default")
      (node (ref "DIGITAL2") (pin "3") (pinfunction "3_3") (pintype "passive"))
      (node (ref "U6") (pin "58") (pinfunction "58_58") (pintype "bidirectional"))
    )
    (net (code "72") (name "Net-(DIGITAL2-Pad4)") (class "Default")
      (node (ref "DIGITAL2") (pin "4") (pinfunction "4_4") (pintype "passive"))
      (node (ref "U6") (pin "57") (pinfunction "57_57") (pintype "bidirectional"))
    )
    (net (code "73") (name "Net-(DIGITAL2-Pad5)") (class "Default")
      (node (ref "DIGITAL2") (pin "5") (pinfunction "5_5") (pintype "passive"))
      (node (ref "U6") (pin "56") (pinfunction "56_56") (pintype "bidirectional"))
    )
    (net (code "74") (name "Net-(DIGITAL2-Pad6)") (class "Default")
      (node (ref "DIGITAL2") (pin "6") (pinfunction "6_6") (pintype "passive"))
      (node (ref "U6") (pin "55") (pinfunction "55_55") (pintype "bidirectional"))
    )
    (net (code "75") (name "Net-(DIGITAL2-Pad7)") (class "Default")
      (node (ref "DIGITAL2") (pin "7") (pinfunction "7_7") (pintype "passive"))
      (node (ref "U6") (pin "54") (pinfunction "54_54") (pintype "bidirectional"))
    )
    (net (code "76") (name "Net-(DIGITAL2-Pad8)") (class "Default")
      (node (ref "DIGITAL2") (pin "8") (pinfunction "8_8") (pintype "passive"))
      (node (ref "U6") (pin "53") (pinfunction "53_53") (pintype "bidirectional"))
    )
    (net (code "77") (name "Net-(HEATPADA-S)") (class "Default")
      (node (ref "HEATPAD") (pin "1") (pinfunction "S_1") (pintype "passive"))
      (node (ref "T1") (pin "1") (pinfunction "E_1") (pintype "passive"))
      (node (ref "T2") (pin "1") (pinfunction "E_1") (pintype "passive"))
    )
    (net (code "78") (name "Net-(IC2-CV)") (class "Default")
      (node (ref "IC2") (pin "5") (pinfunction "CV_5") (pintype "input"))
      (node (ref "RH1") (pin "2") (pinfunction "2_2") (pintype "passive"))
    )
    (net (code "79") (name "Net-(IC2-DIS)") (class "Default")
      (node (ref "IC2") (pin "7") (pinfunction "DIS_7") (pintype "input"))
      (node (ref "RH2") (pin "1") (pinfunction "1_1") (pintype "passive"))
      (node (ref "RH4") (pin "2") (pinfunction "2_2") (pintype "passive"))
    )
    (net (code "80") (name "Net-(IC2-Q)") (class "Default")
      (node (ref "IC2") (pin "3") (pinfunction "Q_3") (pintype "output"))
      (node (ref "RH3") (pin "2") (pinfunction "2_2") (pintype "passive"))
    )
    (net (code "81") (name "Net-(IC2-THR)") (class "Default")
      (node (ref "HUMIDITY") (pin "1") (pinfunction "1_1") (pintype "passive"))
      (node (ref "IC2") (pin "2") (pinfunction "TR_2") (pintype "input"))
      (node (ref "IC2") (pin "6") (pinfunction "THR_6") (pintype "input"))
      (node (ref "RH2") (pin "2") (pinfunction "2_2") (pintype "passive"))
    )
    (net (code "82") (name "Net-(L1-2)") (class "Default")
      (node (ref "L1") (pin "P$2") (pinfunction "2_P$2") (pintype "passive"))
      (node (ref "U$1") (pin "1") (pinfunction "SW_1") (pintype "input"))
      (node (ref "U$1") (pin "2") (pinfunction "SW_2") (pintype "input"))
    )
    (net (code "83") (name "Net-(LED1-PadA)") (class "Default")
      (node (ref "LED1") (pin "A") (pinfunction "A_A") (pintype "passive"))
      (node (ref "R1") (pin "1") (pinfunction "1_1") (pintype "passive"))
    )
    (net (code "84") (name "Net-(LED2-PadA)") (class "Default")
      (node (ref "LED2") (pin "A") (pinfunction "A_A") (pintype "passive"))
      (node (ref "R2") (pin "1") (pinfunction "1_1") (pintype "passive"))
    )
    (net (code "85") (name "Net-(LED3-PadC)") (class "Default")
      (node (ref "LED3") (pin "C") (pinfunction "C_C") (pintype "passive"))
      (node (ref "R6") (pin "2") (pinfunction "2_2") (pintype "passive"))
    )
    (net (code "86") (name "Net-(R16-Pad2)") (class "Default")
      (node (ref "R16") (pin "2") (pinfunction "2_2") (pintype "passive"))
      (node (ref "U6") (pin "63") (pinfunction "63_63") (pintype "bidirectional"))
    )
    (net (code "87") (name "Net-(RG2-Pad1)") (class "Default")
      (node (ref "RG2") (pin "1") (pinfunction "1_1") (pintype "passive"))
      (node (ref "RG3") (pin "2") (pinfunction "2_2") (pintype "passive"))
      (node (ref "TEMP2") (pin "1") (pinfunction "1_1") (pintype "passive"))
    )
    (net (code "88") (name "Net-(U$1-FB)") (class "Default")
      (node (ref "R3") (pin "1") (pinfunction "1_1") (pintype "passive"))
      (node (ref "R5") (pin "2") (pinfunction "2_2") (pintype "passive"))
      (node (ref "U$1") (pin "7") (pinfunction "FB_7") (pintype "input"))
    )
    (net (code "89") (name "Net-(U$1-SS)") (class "Default")
      (node (ref "C4") (pin "1") (pinfunction "1_1") (pintype "passive"))
      (node (ref "U$1") (pin "6") (pinfunction "SS_6") (pintype "input"))
    )
    (net (code "90") (name "Net-(U1-*CHG)") (class "Default")
      (node (ref "LED1") (pin "C") (pinfunction "C_C") (pintype "passive"))
      (node (ref "U1") (pin "8") (pinfunction "*CHG_8") (pintype "output"))
    )
    (net (code "91") (name "Net-(U1-*PG)") (class "Default")
      (node (ref "LED2") (pin "C") (pinfunction "C_C") (pintype "passive"))
      (node (ref "U1") (pin "6") (pinfunction "*PG_6") (pintype "output"))
    )
    (net (code "92") (name "Net-(U1-ISET)") (class "Default")
      (node (ref "R4") (pin "2") (pinfunction "2_2") (pintype "passive"))
      (node (ref "U1") (pin "2") (pinfunction "ISET_2") (pintype "input"))
    )
    (net (code "93") (name "Net-(U1-TS)") (class "Default")
      (node (ref "RT1") (pin "1") (pinfunction "1_1") (pintype "passive"))
      (node (ref "TEMP1") (pin "2") (pinfunction "2_2") (pintype "passive"))
      (node (ref "U1") (pin "5") (pinfunction "TS_5") (pintype "input"))
    )
    (net (code "94") (name "Net-(U1-VDPM)") (class "Default")
      (node (ref "RVDM") (pin "2") (pinfunction "2_2") (pintype "passive"))
      (node (ref "U1") (pin "9") (pinfunction "VDPM_9") (pintype "input"))
    )
    (net (code "95") (name "Net-(U1-VTSB)") (class "Default")
      (node (ref "RT1") (pin "2") (pinfunction "2_2") (pintype "passive"))
      (node (ref "U1") (pin "4") (pinfunction "VTSB_4") (pintype "output"))
    )
    (net (code "96") (name "Net-(U2-BI{slash}TOUT)") (class "Default")
      (node (ref "CG2") (pin "1") (pinfunction "1_1") (pintype "passive"))
      (node (ref "RG1") (pin "1") (pinfunction "1_1") (pintype "passive"))
      (node (ref "RG2") (pin "2") (pinfunction "2_2") (pintype "passive"))
      (node (ref "U2") (pin "1") (pinfunction "BI/TOUT_1") (pintype "bidirectional"))
    )
    (net (code "97") (name "Net-(U2-REG25)") (class "Default")
      (node (ref "CG4") (pin "1") (pinfunction "1_1") (pintype "passive"))
      (node (ref "RG1") (pin "2") (pinfunction "2_2") (pintype "passive"))
      (node (ref "U2") (pin "2") (pinfunction "REG25_2") (pintype "power_in"))
      (node (ref "U2") (pin "5") (pinfunction "VCC_5") (pintype "power_in"))
    )
    (net (code "98") (name "Net-(U2-SRN)") (class "Default")
      (node (ref "CG6") (pin "1") (pinfunction "1_1") (pintype "passive"))
      (node (ref "CG7") (pin "1") (pinfunction "1_1") (pintype "passive"))
      (node (ref "RG5") (pin "2") (pinfunction "2_2") (pintype "passive"))
      (node (ref "U2") (pin "8") (pinfunction "SRN_8") (pintype "input"))
    )
    (net (code "99") (name "Net-(U2-SRP)") (class "Default")
      (node (ref "CG6") (pin "2") (pinfunction "2_2") (pintype "passive"))
      (node (ref "CG8") (pin "2") (pinfunction "2_2") (pintype "passive"))
      (node (ref "RG6") (pin "2") (pinfunction "2_2") (pintype "passive"))
      (node (ref "U2") (pin "7") (pinfunction "SRP_7") (pintype "input"))
    )
    (net (code "100") (name "Net-(U2-TS)") (class "Default")
      (node (ref "CG1") (pin "1") (pinfunction "1_1") (pintype "passive"))
      (node (ref "RG3") (pin "1") (pinfunction "1_1") (pintype "passive"))
      (node (ref "U2") (pin "9") (pinfunction "TS_9") (pintype "input"))
    )
    (net (code "101") (name "Net-(U3-AOUT1)") (class "Default")
      (node (ref "SV1") (pin "1") (pinfunction "1_1") (pintype "passive"))
      (node (ref "U3") (pin "2") (pinfunction "AOUT1_2") (pintype "output"))
    )
    (net (code "102") (name "Net-(U3-AOUT2)") (class "Default")
      (node (ref "SV1") (pin "2") (pinfunction "2_2") (pintype "passive"))
      (node (ref "U3") (pin "3") (pinfunction "AOUT2_3") (pintype "output"))
    )
    (net (code "103") (name "Net-(U3-BOUT1)") (class "Default")
      (node (ref "SV1") (pin "3") (pinfunction "3_3") (pintype "passive"))
      (node (ref "U3") (pin "4") (pinfunction "BOUT1_4") (pintype "output"))
    )
    (net (code "104") (name "Net-(U3-BOUT2)") (class "Default")
      (node (ref "SV1") (pin "4") (pinfunction "4_4") (pintype "passive"))
      (node (ref "U3") (pin "5") (pinfunction "BOUT2_5") (pintype "output"))
    )
    (net (code "105") (name "Net-(U4-AOUT1)") (class "Default")
      (node (ref "SV2") (pin "1") (pinfunction "1_1") (pintype "passive"))
      (node (ref "U4") (pin "2") (pinfunction "AOUT1_2") (pintype "output"))
    )
    (net (code "106") (name "Net-(U4-AOUT2)") (class "Default")
      (node (ref "SV2") (pin "2") (pinfunction "2_2") (pintype "passive"))
      (node (ref "U4") (pin "3") (pinfunction "AOUT2_3") (pintype "output"))
    )
    (net (code "107") (name "Net-(U4-BOUT1)") (class "Default")
      (node (ref "SV2") (pin "3") (pinfunction "3_3") (pintype "passive"))
      (node (ref "U4") (pin "4") (pinfunction "BOUT1_4") (pintype "output"))
    )
    (net (code "108") (name "Net-(U4-BOUT2)") (class "Default")
      (node (ref "SV2") (pin "4") (pinfunction "4_4") (pintype "passive"))
      (node (ref "U4") (pin "5") (pinfunction "BOUT2_5") (pintype "output"))
    )
    (net (code "109") (name "Net-(U5-AOUT1)") (class "Default")
      (node (ref "SV3") (pin "1") (pinfunction "1_1") (pintype "passive"))
      (node (ref "U5") (pin "2") (pinfunction "AOUT1_2") (pintype "output"))
    )
    (net (code "110") (name "Net-(U5-AOUT2)") (class "Default")
      (node (ref "SV3") (pin "2") (pinfunction "2_2") (pintype "passive"))
      (node (ref "U5") (pin "3") (pinfunction "AOUT2_3") (pintype "output"))
    )
    (net (code "111") (name "Net-(U5-BOUT1)") (class "Default")
      (node (ref "SV3") (pin "3") (pinfunction "3_3") (pintype "passive"))
      (node (ref "U5") (pin "4") (pinfunction "BOUT1_4") (pintype "output"))
    )
    (net (code "112") (name "Net-(U5-BOUT2)") (class "Default")
      (node (ref "SV3") (pin "4") (pinfunction "4_4") (pintype "passive"))
      (node (ref "U5") (pin "5") (pinfunction "BOUT2_5") (pintype "output"))
    )
    (net (code "113") (name "Net-(U7-AOUT1)") (class "Default")
      (node (ref "SV4") (pin "1") (pinfunction "1_1") (pintype "passive"))
      (node (ref "U7") (pin "2") (pinfunction "AOUT1_2") (pintype "output"))
    )
    (net (code "114") (name "Net-(U7-AOUT2)") (class "Default")
      (node (ref "SV4") (pin "2") (pinfunction "2_2") (pintype "passive"))
      (node (ref "U7") (pin "3") (pinfunction "AOUT2_3") (pintype "output"))
    )
    (net (code "115") (name "Net-(U7-BOUT1)") (class "Default")
      (node (ref "SV4") (pin "3") (pinfunction "3_3") (pintype "passive"))
      (node (ref "U7") (pin "4") (pinfunction "BOUT1_4") (pintype "output"))
    )
    (net (code "116") (name "Net-(U7-BOUT2)") (class "Default")
      (node (ref "SV4") (pin "4") (pinfunction "4_4") (pintype "passive"))
      (node (ref "U7") (pin "5") (pinfunction "BOUT2_5") (pintype "output"))
    )
    (net (code "117") (name "VCC") (class "Default")
      (node (ref "C1") (pin "1") (pinfunction "1_1") (pintype "passive"))
      (node (ref "SOLAR") (pin "2") (pinfunction "2_2") (pintype "passive"))
      (node (ref "T1") (pin "3") (pinfunction "C_3") (pintype "passive"))
      (node (ref "U1") (pin "1") (pinfunction "VBUS_1") (pintype "bidirectional"))
    )
    (net (code "118") (name "unconnected-(COMPASS-DRDY-Pad15)") (class "Default")
      (node (ref "COMPASS") (pin "15") (pinfunction "DRDY_15") (pintype "input"))
    )
    (net (code "119") (name "unconnected-(MPU-6050-Pad6)") (class "Default")
      (node (ref "MPU-6050") (pin "6") (pinfunction "6_6") (pintype "bidirectional"))
    )
    (net (code "120") (name "unconnected-(MPU-6050-Pad7)") (class "Default")
      (node (ref "MPU-6050") (pin "7") (pinfunction "7_7") (pintype "bidirectional"))
    )
    (net (code "121") (name "unconnected-(MPU-6050-Pad12)") (class "Default")
      (node (ref "MPU-6050") (pin "12") (pinfunction "12_12") (pintype "bidirectional"))
    )
    (net (code "122") (name "unconnected-(MPU-6050-Pad22)") (class "Default")
      (node (ref "MPU-6050") (pin "22") (pinfunction "22_22") (pintype "bidirectional"))
    )
    (net (code "123") (name "unconnected-(U$1-HYS-Pad8)") (class "Default")
      (node (ref "U$1") (pin "8") (pinfunction "HYS_8") (pintype "input"))
    )
    (net (code "124") (name "unconnected-(U2-BAT_LOW{slash}BAT_GD-Pad12)") (class "Default")
      (node (ref "U2") (pin "12") (pinfunction "BAT_LOW/BAT_GD_12") (pintype "output"))
    )
    (net (code "125") (name "unconnected-(U6-Pad7)") (class "Default")
      (node (ref "U6") (pin "7") (pinfunction "7_7") (pintype "bidirectional"))
    )
    (net (code "126") (name "unconnected-(U6-Pad8)") (class "Default")
      (node (ref "U6") (pin "8") (pinfunction "8_8") (pintype "bidirectional"))
    )
    (net (code "127") (name "unconnected-(U6-Pad62)") (class "Default")
      (node (ref "U6") (pin "62") (pinfunction "62_62") (pintype "bidirectional"))
    )
    (net (code "128") (name "unconnected-(U6-Pad64)") (class "Default")
      (node (ref "U6") (pin "64") (pinfunction "64_64") (pintype "bidirectional"))
    )
    (net (code "129") (name "unconnected-(U6-Pad69)") (class "Default")
      (node (ref "U6") (pin "69") (pinfunction "69_69") (pintype "bidirectional"))
    )
    (net (code "130") (name "unconnected-(U6-Pad70)") (class "Default")
      (node (ref "U6") (pin "70") (pinfunction "70_70") (pintype "bidirectional"))
    )
    (net (code "131") (name "unconnected-(U6-Pad72)") (class "Default")
      (node (ref "U6") (pin "72") (pinfunction "72_72") (pintype "bidirectional"))
    )
    (net (code "132") (name "unconnected-(U6-Pad73)") (class "Default")
      (node (ref "U6") (pin "73") (pinfunction "73_73") (pintype "bidirectional"))
    )
    (net (code "133") (name "unconnected-(U6-Pad74)") (class "Default")
      (node (ref "U6") (pin "74") (pinfunction "74_74") (pintype "bidirectional"))
    )
    (net (code "134") (name "unconnected-(U6-Pad75)") (class "Default")
      (node (ref "U6") (pin "75") (pinfunction "75_75") (pintype "bidirectional"))
    )
  )
)
